# SHIELD-uSD-MIKROE-PMOD.net
KiCad netlist of a schematic drawn in Altium Designer
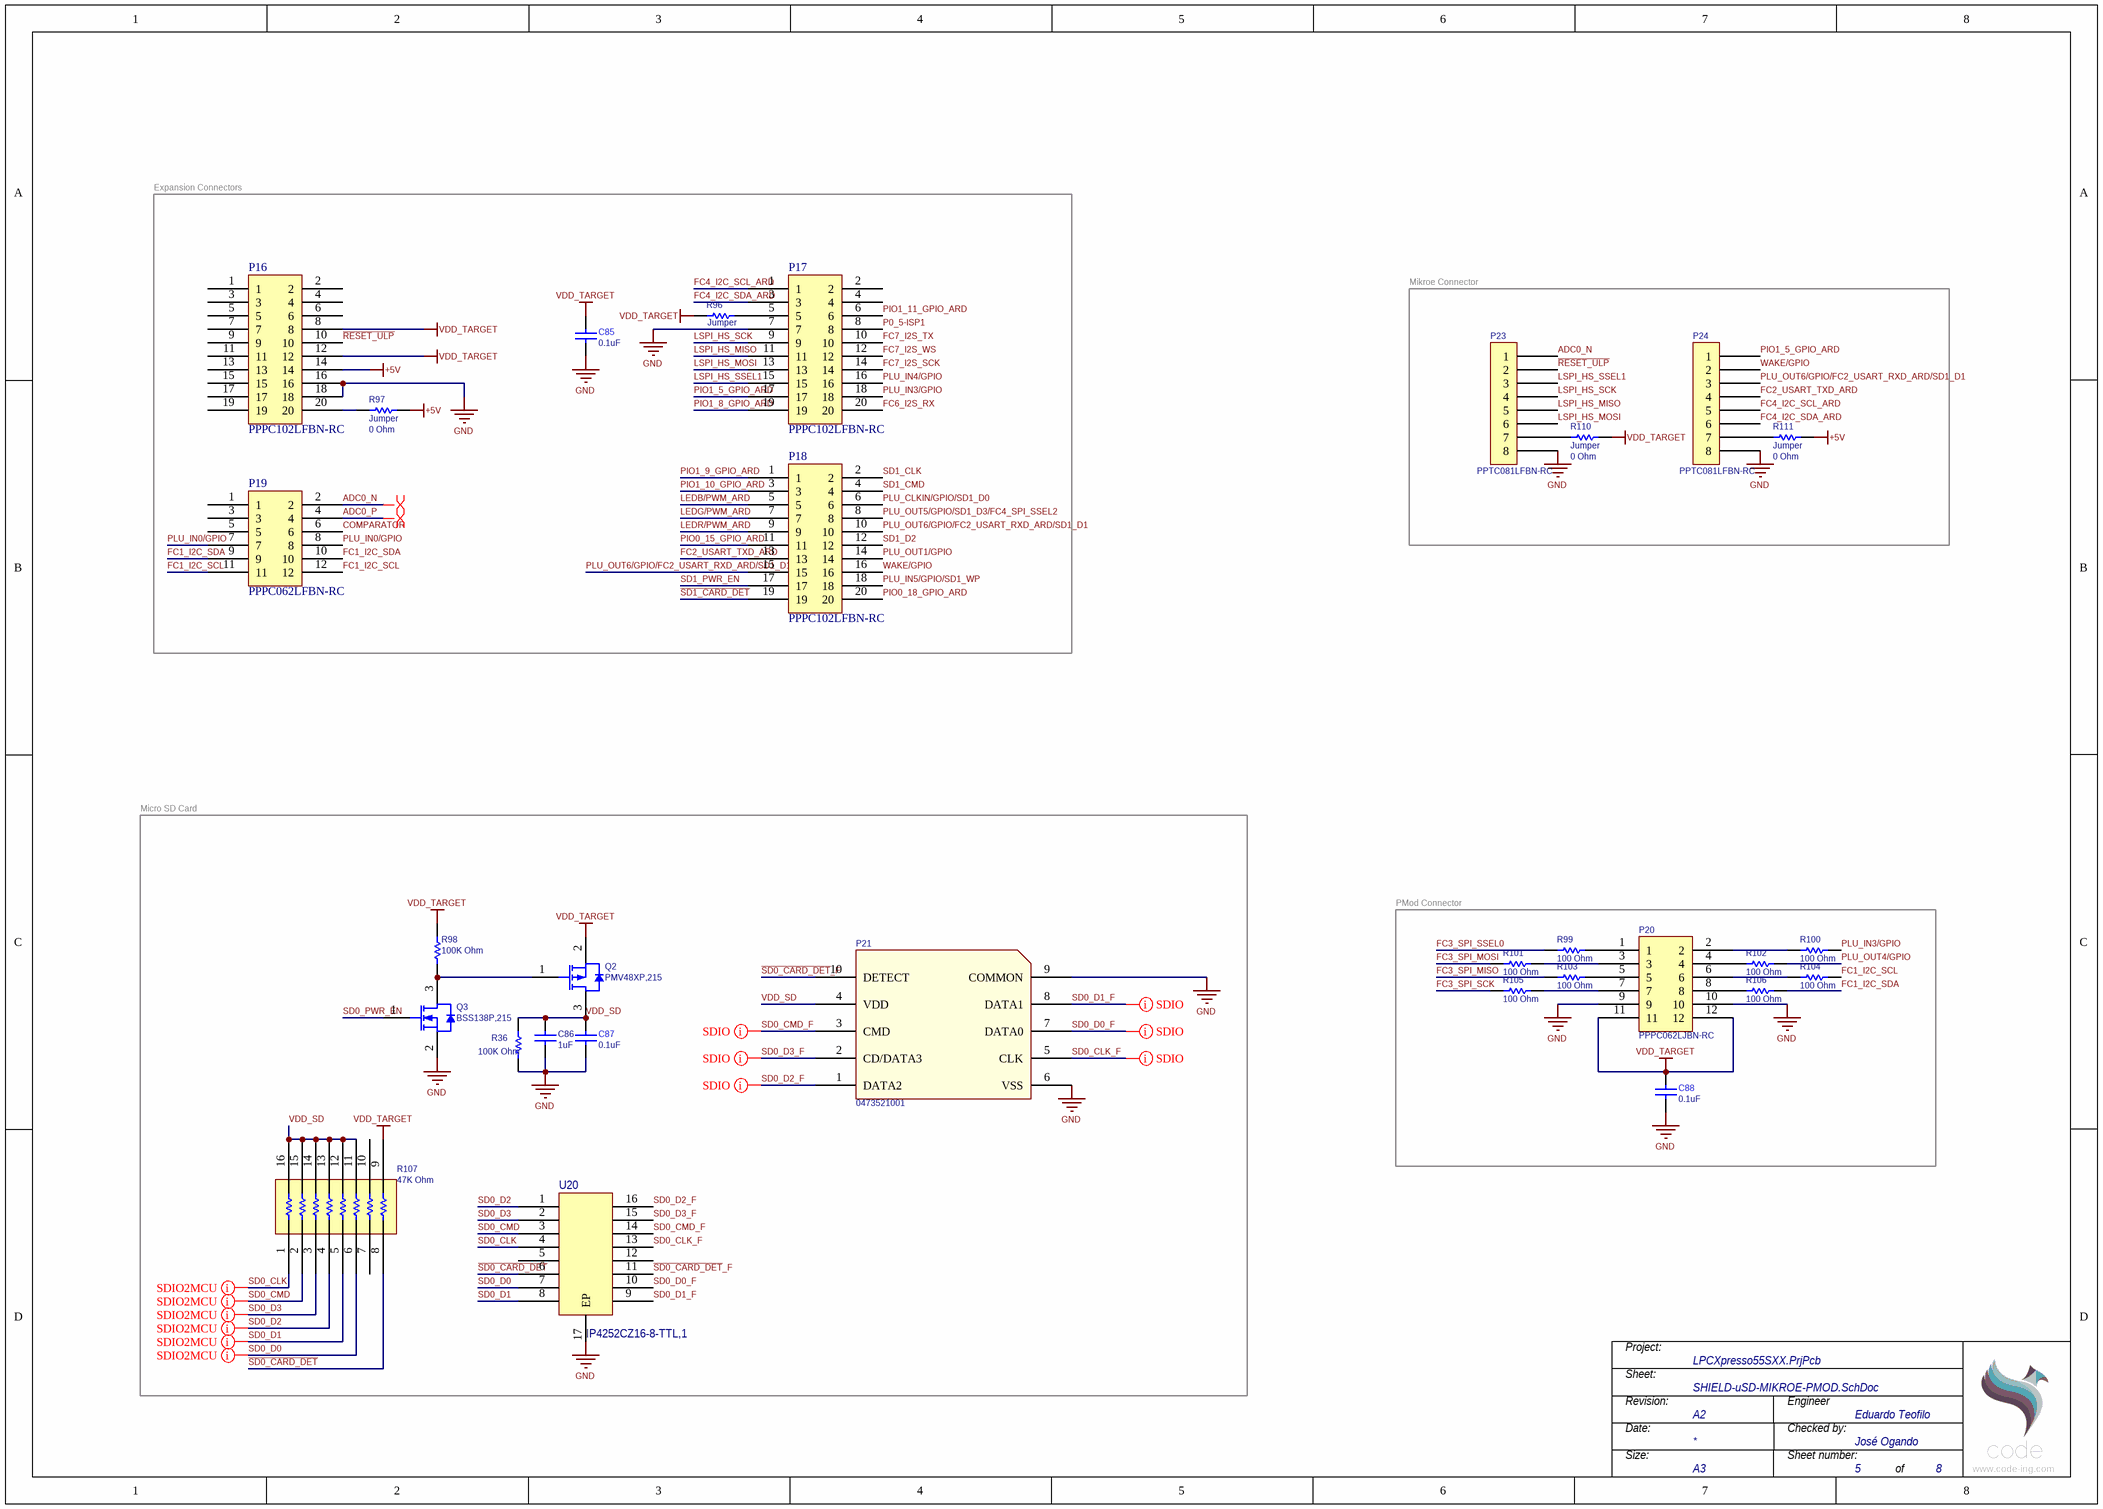
[diagram p0: SHIELD-uSD-MIKROE-PMOD.SchDoc]

(export (version "E")
  (design (tool "Eeschema 10.0.6"))
  (components
    (comp (ref "C85")
      (value "0.1uF")
      (footprint "CAPC1005")
      (description "Capacitor, Yageo, Ceramic, 0.1uF 10% 16V 0402 (1005) X7R")
      (fields
        (field (name "TOLERANCE") "10 %")
        (field (name "Comment") "CC0402KRX7R7BB104")
        (field (name "PUBLISHER") "Altium")
      )
      (libsource (lib "Altium Content Vault") (part "CMP-0001-00074-1"))
    )
    (comp (ref "C86")
      (value "1uF")
      (footprint "CAPC0402(1005)60_L")
      (description "CAP 1uF 10V -20% to +80% 0402 (1005 Metric) Thickness 0.6mm SMD")
      (fields (field (name "TOLERANCE") "-20% to +80%") (field (name "Comment") "CAP 1uF 10V 0402(1005)"))
      (libsource (lib "Altium Content Vault") (part "CMP-1034-02118-1"))
    )
    (comp (ref "C87")
      (value "0.1uF")
      (footprint "CAPC1005")
      (description "Capacitor, Yageo, Ceramic, 0.1uF 10% 16V 0402 (1005) X7R")
      (fields
        (field (name "TOLERANCE") "10 %")
        (field (name "Comment") "CC0402KRX7R7BB104")
        (field (name "PUBLISHER") "Altium")
      )
      (libsource (lib "Altium Content Vault") (part "CMP-0001-00074-1"))
    )
    (comp (ref "C88")
      (value "0.1uF")
      (footprint "CAPC1005")
      (description "Capacitor, Yageo, Ceramic, 0.1uF 10% 16V 0402 (1005) X7R")
      (fields
        (field (name "TOLERANCE") "10 %")
        (field (name "Comment") "CC0402KRX7R7BB104")
        (field (name "PUBLISHER") "Altium")
      )
      (libsource (lib "Altium Content Vault") (part "CMP-0001-00074-1"))
    )
    (comp (ref "P16")
      (value "PPPC102LFBN-RC")
      (footprint "PPPC102LFBN-RC")
      (description "CONN HEADER FMAL 20PS.1\" DL GOLD")
      (fields
        (field (name "MANUFACTURER") "Sullins Connector Solutions")
        (field (name "CREATED BY") "jvelasquez")
        (field (name "MODIFIED BY") "*")
      )
      (libsource (lib "Rectangular - Headers, Receptacles, Female Sockets") (part "PPPC102LFBN-RC"))
    )
    (comp (ref "P17")
      (value "PPPC102LFBN-RC")
      (footprint "PPPC102LFBN-RC")
      (description "CONN HEADER FMAL 20PS.1\" DL GOLD")
      (fields
        (field (name "MANUFACTURER") "Sullins Connector Solutions")
        (field (name "CREATED BY") "jvelasquez")
        (field (name "MODIFIED BY") "*")
      )
      (libsource (lib "Rectangular - Headers, Receptacles, Female Sockets") (part "PPPC102LFBN-RC"))
    )
    (comp (ref "P18")
      (value "PPPC102LFBN-RC")
      (footprint "PPPC102LFBN-RC")
      (description "CONN HEADER FMAL 20PS.1\" DL GOLD")
      (fields
        (field (name "MANUFACTURER") "Sullins Connector Solutions")
        (field (name "CREATED BY") "jvelasquez")
        (field (name "MODIFIED BY") "*")
      )
      (libsource (lib "Rectangular - Headers, Receptacles, Female Sockets") (part "PPPC102LFBN-RC"))
    )
    (comp (ref "P19")
      (value "PPPC062LFBN-RC")
      (footprint "PPPC062LFBN-RC")
      (description "CONN HEADER FMAL 12PS.1\" DL GOLD")
      (fields
        (field (name "MANUFACTURER") "Sullins Connector Solutions")
        (field (name "CREATED BY") "jvelasquez")
        (field (name "MODIFIED BY") "*")
      )
      (libsource (lib "Rectangular - Headers, Receptacles, Female Sockets") (part "PPPC062LFBN-RC"))
    )
    (comp (ref "P20")
      (value "PPPC062LJBN-RC")
      (footprint "PPPC062LJBN-RC")
      (description "CONN FEMALE 12POSDL .1\" R/A GOLD")
      (fields
        (field (name "MANUFACTURER") "Sullins Connector Solutions")
        (field (name "CREATED BY") "eteofilo")
        (field (name "MODIFIED BY") "*")
      )
      (libsource (lib "Rectangular - Headers, Receptacles, Female Sockets") (part "PPPC062LJBN-RC"))
    )
    (comp (ref "P21")
      (value "0473521001")
      (footprint "0473521001")
      (description "CONN MICRO SD CARD PUSH-PUSH R/A")
      (fields
        (field (name "MANUFACTURER") "Molex Inc")
        (field (name "CREATED BY") "eteofilo")
        (field (name "MODIFIED BY") "*")
      )
      (libsource (lib "Memory - PC Cards - Connectors") (part "0473521001"))
    )
    (comp (ref "P23")
      (value "PPTC081LFBN-RC")
      (footprint "Header 8x1")
      (description "CONN HEADER FEMALE 8POS .1\" TIN")
      (fields
        (field (name "MANUFACTURER") "Sullins Connector Solutions")
        (field (name "CREATED BY") "eteofilo")
        (field (name "MODIFIED BY") "*")
      )
      (libsource (lib "Rectangular - Headers, Receptacles, Female Sockets") (part "PPTC081LFBN-RC"))
    )
    (comp (ref "P24")
      (value "PPTC081LFBN-RC")
      (footprint "Header 8x1")
      (description "CONN HEADER FEMALE 8POS .1\" TIN")
      (fields
        (field (name "MANUFACTURER") "Sullins Connector Solutions")
        (field (name "CREATED BY") "eteofilo")
        (field (name "MODIFIED BY") "*")
      )
      (libsource (lib "Rectangular - Headers, Receptacles, Female Sockets") (part "PPTC081LFBN-RC"))
    )
    (comp (ref "Q2")
      (value "PMV48XP,215")
      (footprint "NXP-SOT23_M")
      (description "P-Channel Trench MOSFET, -20 V, -3.5 A, -55 to 150 degC, 3-Pin SOT23, Tape and Reel")
      (fields (field (name "MANUFACTURER") "NXP Semiconductors"))
      (libsource (lib "Altium Content Vault") (part "CMP-1258-00160-1"))
    )
    (comp (ref "Q3")
      (value "BSS138P,215")
      (footprint "NXP-SOT23_N")
      (description "N-Channel Trench MOSFET, 60 V, 0.36 A, -55 to 150 degC, 3-Pin SOT23, Tape and Reel")
      (fields (field (name "MANUFACTURER") "NXP Semiconductors"))
      (libsource (lib "Altium Content Vault") (part "NXP-NMOS-GSD-3_B"))
    )
    (comp (ref "R36")
      (value "100K Ohm")
      (footprint "RESC1005X40X25LL05T05")
      (description "Chip Resistor, 100 KOhm, +/- 1%, 100 mW, -55 to 155 degC, 0402 (1005 Metric), RoHS, Tape and Reel")
      (fields (field (name "TOLERANCE") "1%") (field (name "MANUFACTURER") "Basic Passives"))
      (libsource (lib "Altium Content Vault") (part "CMP-2002-00608-3"))
    )
    (comp (ref "R96")
      (value "Jumper")
      (footprint "RESC0402(1005)_L")
      (description "Jumper 0402 (1005 Metric)")
      (fields (field (name "TOLERANCE") "None"))
      (libsource (lib "Altium Content Vault") (part "CMP-1011-00001-1"))
    )
    (comp (ref "R97")
      (value "Jumper")
      (footprint "RESC0402(1005)_L")
      (description "Jumper 0402 (1005 Metric)")
      (fields (field (name "TOLERANCE") "None") (field (name "ALTIUM_VALUE") "0 Ohm"))
      (libsource (lib "Altium Content Vault") (part "CMP-1011-00001-1"))
    )
    (comp (ref "R98")
      (value "100K Ohm")
      (footprint "RESC1005X40X25LL05T05")
      (description "Chip Resistor, 100 KOhm, +/- 1%, 100 mW, -55 to 155 degC, 0402 (1005 Metric), RoHS, Tape and Reel")
      (fields (field (name "TOLERANCE") "1%") (field (name "MANUFACTURER") "Basic Passives"))
      (libsource (lib "Altium Content Vault") (part "CMP-2002-00608-3"))
    )
    (comp (ref "R99")
      (value "100 Ohm")
      (footprint "RESC0402(1005)_L")
      (description "100R 0.063W 5% 0402 (1005 Metric)  SMD")
      (fields (field (name "POWER") "0.063 W") (field (name "TOLERANCE") "5 %"))
      (libsource (lib "Altium Content Vault") (part "CMP-1011-00050-1"))
    )
    (comp (ref "R100")
      (value "100 Ohm")
      (footprint "RESC0402(1005)_L")
      (description "100R 0.063W 5% 0402 (1005 Metric)  SMD")
      (fields (field (name "POWER") "0.063 W") (field (name "TOLERANCE") "5 %"))
      (libsource (lib "Altium Content Vault") (part "CMP-1011-00050-1"))
    )
    (comp (ref "R101")
      (value "100 Ohm")
      (footprint "RESC0402(1005)_L")
      (description "100R 0.063W 5% 0402 (1005 Metric)  SMD")
      (fields (field (name "POWER") "0.063 W") (field (name "TOLERANCE") "5 %"))
      (libsource (lib "Altium Content Vault") (part "CMP-1011-00050-1"))
    )
    (comp (ref "R102")
      (value "100 Ohm")
      (footprint "RESC0402(1005)_L")
      (description "100R 0.063W 5% 0402 (1005 Metric)  SMD")
      (fields (field (name "POWER") "0.063 W") (field (name "TOLERANCE") "5 %"))
      (libsource (lib "Altium Content Vault") (part "CMP-1011-00050-1"))
    )
    (comp (ref "R103")
      (value "100 Ohm")
      (footprint "RESC0402(1005)_L")
      (description "100R 0.063W 5% 0402 (1005 Metric)  SMD")
      (fields (field (name "POWER") "0.063 W") (field (name "TOLERANCE") "5 %"))
      (libsource (lib "Altium Content Vault") (part "CMP-1011-00050-1"))
    )
    (comp (ref "R104")
      (value "100 Ohm")
      (footprint "RESC0402(1005)_L")
      (description "100R 0.063W 5% 0402 (1005 Metric)  SMD")
      (fields (field (name "POWER") "0.063 W") (field (name "TOLERANCE") "5 %"))
      (libsource (lib "Altium Content Vault") (part "CMP-1011-00050-1"))
    )
    (comp (ref "R105")
      (value "100 Ohm")
      (footprint "RESC0402(1005)_L")
      (description "100R 0.063W 5% 0402 (1005 Metric)  SMD")
      (fields (field (name "POWER") "0.063 W") (field (name "TOLERANCE") "5 %"))
      (libsource (lib "Altium Content Vault") (part "CMP-1011-00050-1"))
    )
    (comp (ref "R106")
      (value "100 Ohm")
      (footprint "RESC0402(1005)_L")
      (description "100R 0.063W 5% 0402 (1005 Metric)  SMD")
      (fields (field (name "POWER") "0.063 W") (field (name "TOLERANCE") "5 %"))
      (libsource (lib "Altium Content Vault") (part "CMP-1011-00050-1"))
    )
    (comp (ref "R107")
      (value "47K Ohm")
      (footprint "EXB-2HV473JV")
      (description "RES ARRAY 8 RES 47K OHM 1506")
      (fields
        (field (name "MANUFACTURER") "Panasonic Electronic Components")
        (field (name "MANUFACTURER PART #") "EXB-2HV473JV")
        (field (name "CREATED BY") "eteofilo")
        (field (name "MODIFIED BY") "*")
      )
      (libsource (lib "Resistor Networks, Arrays") (part "EXB-2HV473JV"))
    )
    (comp (ref "R110")
      (value "Jumper")
      (footprint "RESC0402(1005)_L")
      (description "Jumper 0402 (1005 Metric)")
      (fields (field (name "TOLERANCE") "None") (field (name "ALTIUM_VALUE") "0 Ohm"))
      (libsource (lib "Altium Content Vault") (part "CMP-1011-00001-1"))
    )
    (comp (ref "R111")
      (value "Jumper")
      (footprint "RESC0402(1005)_L")
      (description "Jumper 0402 (1005 Metric)")
      (fields (field (name "TOLERANCE") "None") (field (name "ALTIUM_VALUE") "0 Ohm"))
      (libsource (lib "Altium Content Vault") (part "CMP-1011-00001-1"))
    )
    (comp (ref "U20")
      (value "IP4252CZ16-8-TTL,1")
      (footprint "HUSON16")
      (fields
        (field (name "MANUFACTURER") "Nexperia USA Inc.")
        (field (name "CREATED BY") "eteofilo")
        (field (name "MODIFIED BY") "*")
      )
      (libsource (lib "EMI RFI Filters (LC, RC Networks)") (part "IP4252CZ16-8-TTL,1"))
    )
  )
  (nets
    (net (code "1") (name "+5V") (class "Default")
      (node (ref "P16") (pin "14") (pinfunction "14_14") (pintype "passive"))
      (node (ref "R111") (pin "1") (pinfunction "1_1") (pintype "passive"))
      (node (ref "R97") (pin "1") (pinfunction "1_1") (pintype "passive"))
    )
    (net (code "2") (name "/ADC0_N") (class "Default")
      (node (ref "P19") (pin "2") (pinfunction "2_2") (pintype "passive"))
      (node (ref "P23") (pin "1") (pinfunction "1_1") (pintype "passive"))
    )
    (net (code "3") (name "/ADC0_P") (class "Default")
      (node (ref "P19") (pin "4") (pinfunction "4_4") (pintype "passive"))
    )
    (net (code "4") (name "/COMPARATOR") (class "Default")
      (node (ref "P19") (pin "6") (pinfunction "6_6") (pintype "passive"))
    )
    (net (code "5") (name "/FC1_I2C_SCL") (class "Default")
      (node (ref "P19") (pin "11") (pinfunction "11_11") (pintype "passive"))
      (node (ref "P19") (pin "12") (pinfunction "12_12") (pintype "passive"))
      (node (ref "R104") (pin "2") (pinfunction "2_2") (pintype "passive"))
    )
    (net (code "6") (name "/FC1_I2C_SDA") (class "Default")
      (node (ref "P19") (pin "10") (pinfunction "10_10") (pintype "passive"))
      (node (ref "P19") (pin "9") (pinfunction "9_9") (pintype "passive"))
      (node (ref "R106") (pin "2") (pinfunction "2_2") (pintype "passive"))
    )
    (net (code "7") (name "/FC2_USART_TXD_ARD") (class "Default")
      (node (ref "P18") (pin "13") (pinfunction "13_13") (pintype "passive"))
      (node (ref "P24") (pin "4") (pinfunction "4_4") (pintype "passive"))
    )
    (net (code "8") (name "/FC3_SPI_MISO") (class "Default")
      (node (ref "R103") (pin "1") (pinfunction "1_1") (pintype "passive"))
    )
    (net (code "9") (name "/FC3_SPI_MOSI") (class "Default")
      (node (ref "R101") (pin "1") (pinfunction "1_1") (pintype "passive"))
    )
    (net (code "10") (name "/FC3_SPI_SCK") (class "Default")
      (node (ref "R105") (pin "1") (pinfunction "1_1") (pintype "passive"))
    )
    (net (code "11") (name "/FC3_SPI_SSEL0") (class "Default")
      (node (ref "R99") (pin "1") (pinfunction "1_1") (pintype "passive"))
    )
    (net (code "12") (name "/FC4_I2C_SCL_ARD") (class "Default")
      (node (ref "P17") (pin "1") (pinfunction "1_1") (pintype "passive"))
      (node (ref "P24") (pin "5") (pinfunction "5_5") (pintype "passive"))
    )
    (net (code "13") (name "/FC4_I2C_SDA_ARD") (class "Default")
      (node (ref "P17") (pin "3") (pinfunction "3_3") (pintype "passive"))
      (node (ref "P24") (pin "6") (pinfunction "6_6") (pintype "passive"))
    )
    (net (code "14") (name "/FC6_I2S_RX") (class "Default")
      (node (ref "P17") (pin "20") (pinfunction "20_20") (pintype "passive"))
    )
    (net (code "15") (name "/FC7_I2S_SCK") (class "Default")
      (node (ref "P17") (pin "14") (pinfunction "14_14") (pintype "passive"))
    )
    (net (code "16") (name "/FC7_I2S_TX") (class "Default")
      (node (ref "P17") (pin "10") (pinfunction "10_10") (pintype "passive"))
    )
    (net (code "17") (name "/FC7_I2S_WS") (class "Default")
      (node (ref "P17") (pin "12") (pinfunction "12_12") (pintype "passive"))
    )
    (net (code "18") (name "/LEDB{slash}PWM_ARD") (class "Default")
      (node (ref "P18") (pin "5") (pinfunction "5_5") (pintype "passive"))
    )
    (net (code "19") (name "/LEDG{slash}PWM_ARD") (class "Default")
      (node (ref "P18") (pin "7") (pinfunction "7_7") (pintype "passive"))
    )
    (net (code "20") (name "/LEDR{slash}PWM_ARD") (class "Default")
      (node (ref "P18") (pin "9") (pinfunction "9_9") (pintype "passive"))
    )
    (net (code "21") (name "/LSPI_HS_MISO") (class "Default")
      (node (ref "P17") (pin "11") (pinfunction "11_11") (pintype "passive"))
      (node (ref "P23") (pin "5") (pinfunction "5_5") (pintype "passive"))
    )
    (net (code "22") (name "/LSPI_HS_MOSI") (class "Default")
      (node (ref "P17") (pin "13") (pinfunction "13_13") (pintype "passive"))
      (node (ref "P23") (pin "6") (pinfunction "6_6") (pintype "passive"))
    )
    (net (code "23") (name "/LSPI_HS_SCK") (class "Default")
      (node (ref "P17") (pin "9") (pinfunction "9_9") (pintype "passive"))
      (node (ref "P23") (pin "4") (pinfunction "4_4") (pintype "passive"))
    )
    (net (code "24") (name "/LSPI_HS_SSEL1") (class "Default")
      (node (ref "P17") (pin "15") (pinfunction "15_15") (pintype "passive"))
      (node (ref "P23") (pin "3") (pinfunction "3_3") (pintype "passive"))
    )
    (net (code "25") (name "/P0_5-ISP1") (class "Default")
      (node (ref "P17") (pin "8") (pinfunction "8_8") (pintype "passive"))
    )
    (net (code "26") (name "/PIO0_15_GPIO_ARD") (class "Default")
      (node (ref "P18") (pin "11") (pinfunction "11_11") (pintype "passive"))
    )
    (net (code "27") (name "/PIO0_18_GPIO_ARD") (class "Default")
      (node (ref "P18") (pin "20") (pinfunction "20_20") (pintype "passive"))
    )
    (net (code "28") (name "/PIO1_5_GPIO_ARD") (class "Default")
      (node (ref "P17") (pin "17") (pinfunction "17_17") (pintype "passive"))
      (node (ref "P24") (pin "1") (pinfunction "1_1") (pintype "passive"))
    )
    (net (code "29") (name "/PIO1_8_GPIO_ARD") (class "Default")
      (node (ref "P17") (pin "19") (pinfunction "19_19") (pintype "passive"))
    )
    (net (code "30") (name "/PIO1_9_GPIO_ARD") (class "Default")
      (node (ref "P18") (pin "1") (pinfunction "1_1") (pintype "passive"))
    )
    (net (code "31") (name "/PIO1_10_GPIO_ARD") (class "Default")
      (node (ref "P18") (pin "3") (pinfunction "3_3") (pintype "passive"))
    )
    (net (code "32") (name "/PIO1_11_GPIO_ARD") (class "Default")
      (node (ref "P17") (pin "6") (pinfunction "6_6") (pintype "passive"))
    )
    (net (code "33") (name "/PLU_CLKIN{slash}GPIO{slash}SD1_D0") (class "Default")
      (node (ref "P18") (pin "6") (pinfunction "6_6") (pintype "passive"))
    )
    (net (code "34") (name "/PLU_IN0{slash}GPIO") (class "Default")
      (node (ref "P19") (pin "7") (pinfunction "7_7") (pintype "passive"))
      (node (ref "P19") (pin "8") (pinfunction "8_8") (pintype "passive"))
    )
    (net (code "35") (name "/PLU_IN3{slash}GPIO") (class "Default")
      (node (ref "P17") (pin "18") (pinfunction "18_18") (pintype "passive"))
      (node (ref "R100") (pin "2") (pinfunction "2_2") (pintype "passive"))
    )
    (net (code "36") (name "/PLU_IN4{slash}GPIO") (class "Default")
      (node (ref "P17") (pin "16") (pinfunction "16_16") (pintype "passive"))
    )
    (net (code "37") (name "/PLU_IN5{slash}GPIO{slash}SD1_WP") (class "Default")
      (node (ref "P18") (pin "18") (pinfunction "18_18") (pintype "passive"))
    )
    (net (code "38") (name "/PLU_OUT1{slash}GPIO") (class "Default")
      (node (ref "P18") (pin "14") (pinfunction "14_14") (pintype "passive"))
    )
    (net (code "39") (name "/PLU_OUT4{slash}GPIO") (class "Default")
      (node (ref "R102") (pin "2") (pinfunction "2_2") (pintype "passive"))
    )
    (net (code "40") (name "/PLU_OUT5{slash}GPIO{slash}SD1_D3{slash}FC4_SPI_SSEL2") (class "Default")
      (node (ref "P18") (pin "8") (pinfunction "8_8") (pintype "passive"))
    )
    (net (code "41") (name "/PLU_OUT6{slash}GPIO{slash}FC2_USART_RXD_ARD{slash}SD1_D1") (class "Default")
      (node (ref "P18") (pin "10") (pinfunction "10_10") (pintype "passive"))
      (node (ref "P18") (pin "15") (pinfunction "15_15") (pintype "passive"))
      (node (ref "P24") (pin "3") (pinfunction "3_3") (pintype "passive"))
    )
    (net (code "42") (name "/SD0_CLK") (class "Default")
      (node (ref "R107") (pin "1") (pinfunction "1_1") (pintype "passive"))
      (node (ref "U20") (pin "4") (pintype "passive"))
    )
    (net (code "43") (name "/SD0_CLK_F") (class "Default")
      (node (ref "P21") (pin "5") (pinfunction "CLK_5") (pintype "passive"))
      (node (ref "U20") (pin "13") (pintype "passive"))
    )
    (net (code "44") (name "/SD0_CMD") (class "Default")
      (node (ref "R107") (pin "2") (pinfunction "2_2") (pintype "passive"))
      (node (ref "U20") (pin "3") (pintype "passive"))
    )
    (net (code "45") (name "/SD0_CMD_F") (class "Default")
      (node (ref "P21") (pin "3") (pinfunction "CMD_3") (pintype "passive"))
      (node (ref "U20") (pin "14") (pintype "passive"))
    )
    (net (code "46") (name "/SD0_D0") (class "Default")
      (node (ref "R107") (pin "6") (pinfunction "6_6") (pintype "passive"))
      (node (ref "U20") (pin "7") (pintype "passive"))
    )
    (net (code "47") (name "/SD0_D0_F") (class "Default")
      (node (ref "P21") (pin "7") (pinfunction "DATA0_7") (pintype "passive"))
      (node (ref "U20") (pin "10") (pintype "passive"))
    )
    (net (code "48") (name "/SD0_D1") (class "Default")
      (node (ref "R107") (pin "5") (pinfunction "5_5") (pintype "passive"))
      (node (ref "U20") (pin "8") (pintype "passive"))
    )
    (net (code "49") (name "/SD0_D1_F") (class "Default")
      (node (ref "P21") (pin "8") (pinfunction "DATA1_8") (pintype "passive"))
      (node (ref "U20") (pin "9") (pintype "passive"))
    )
    (net (code "50") (name "/SD0_D2") (class "Default")
      (node (ref "R107") (pin "4") (pinfunction "4_4") (pintype "passive"))
      (node (ref "U20") (pin "1") (pintype "passive"))
    )
    (net (code "51") (name "/SD0_D2_F") (class "Default")
      (node (ref "P21") (pin "1") (pinfunction "DATA2_1") (pintype "passive"))
      (node (ref "U20") (pin "16") (pintype "passive"))
    )
    (net (code "52") (name "/SD0_D3") (class "Default")
      (node (ref "R107") (pin "3") (pinfunction "3_3") (pintype "passive"))
      (node (ref "U20") (pin "2") (pintype "passive"))
    )
    (net (code "53") (name "/SD0_D3_F") (class "Default")
      (node (ref "P21") (pin "2") (pinfunction "CD/DATA3_2") (pintype "passive"))
      (node (ref "U20") (pin "15") (pintype "passive"))
    )
    (net (code "54") (name "/SD0_PWR_EN") (class "Default")
      (node (ref "Q3") (pin "1") (pinfunction "G_1") (pintype "passive"))
    )
    (net (code "55") (name "/SD1_CLK") (class "Default")
      (node (ref "P18") (pin "2") (pinfunction "2_2") (pintype "passive"))
    )
    (net (code "56") (name "/SD1_CMD") (class "Default")
      (node (ref "P18") (pin "4") (pinfunction "4_4") (pintype "passive"))
    )
    (net (code "57") (name "/SD1_D2") (class "Default")
      (node (ref "P18") (pin "12") (pinfunction "12_12") (pintype "passive"))
    )
    (net (code "58") (name "/SD1_PWR_EN") (class "Default")
      (node (ref "P18") (pin "17") (pinfunction "17_17") (pintype "passive"))
    )
    (net (code "59") (name "/VDD_SD") (class "Default")
      (node (ref "C86") (pin "2") (pinfunction "2_2") (pintype "passive"))
      (node (ref "C87") (pin "1") (pinfunction "1_1") (pintype "passive"))
      (node (ref "P21") (pin "4") (pinfunction "VDD_4") (pintype "passive"))
      (node (ref "Q2") (pin "3") (pinfunction "D_3") (pintype "passive"))
      (node (ref "R107") (pin "11") (pinfunction "11_11") (pintype "passive"))
      (node (ref "R107") (pin "12") (pinfunction "12_12") (pintype "passive"))
      (node (ref "R107") (pin "13") (pinfunction "13_13") (pintype "passive"))
      (node (ref "R107") (pin "14") (pinfunction "14_14") (pintype "passive"))
      (node (ref "R107") (pin "15") (pinfunction "15_15") (pintype "passive"))
      (node (ref "R107") (pin "16") (pinfunction "16_16") (pintype "passive"))
      (node (ref "R36") (pin "2") (pinfunction "2_2") (pintype "passive"))
    )
    (net (code "60") (name "/WAKE{slash}GPIO") (class "Default")
      (node (ref "P18") (pin "16") (pinfunction "16_16") (pintype "passive"))
      (node (ref "P24") (pin "2") (pinfunction "2_2") (pintype "passive"))
    )
    (net (code "61") (name "/~{RESET_ULP}") (class "Default")
      (node (ref "P16") (pin "10") (pinfunction "10_10") (pintype "passive"))
      (node (ref "P23") (pin "2") (pinfunction "2_2") (pintype "passive"))
    )
    (net (code "62") (name "/~{SD0_CARD_DET}") (class "Default")
      (node (ref "R107") (pin "8") (pinfunction "8_8") (pintype "passive"))
      (node (ref "U20") (pin "6") (pintype "passive"))
    )
    (net (code "63") (name "/~{SD0_CARD_DET}_F") (class "Default")
      (node (ref "P21") (pin "10") (pinfunction "DETECT_10") (pintype "passive"))
      (node (ref "U20") (pin "11") (pintype "passive"))
    )
    (net (code "64") (name "/~{SD1_CARD_DET}") (class "Default")
      (node (ref "P18") (pin "19") (pinfunction "19_19") (pintype "passive"))
    )
    (net (code "65") (name "GND") (class "Default")
      (node (ref "C85") (pin "2") (pinfunction "2_2") (pintype "passive"))
      (node (ref "C86") (pin "1") (pinfunction "1_1") (pintype "passive"))
      (node (ref "C87") (pin "2") (pinfunction "2_2") (pintype "passive"))
      (node (ref "C88") (pin "2") (pinfunction "2_2") (pintype "passive"))
      (node (ref "P16") (pin "16") (pinfunction "16_16") (pintype "passive"))
      (node (ref "P16") (pin "18") (pinfunction "18_18") (pintype "passive"))
      (node (ref "P17") (pin "7") (pinfunction "7_7") (pintype "passive"))
      (node (ref "P20") (pin "10") (pinfunction "10_10") (pintype "passive"))
      (node (ref "P20") (pin "9") (pinfunction "9_9") (pintype "passive"))
      (node (ref "P21") (pin "6") (pinfunction "VSS_6") (pintype "passive"))
      (node (ref "P21") (pin "9") (pinfunction "COMMON_9") (pintype "passive"))
      (node (ref "P23") (pin "8") (pinfunction "8_8") (pintype "passive"))
      (node (ref "P24") (pin "8") (pinfunction "8_8") (pintype "passive"))
      (node (ref "Q3") (pin "2") (pinfunction "S_2") (pintype "passive"))
      (node (ref "R36") (pin "1") (pinfunction "1_1") (pintype "passive"))
      (node (ref "U20") (pin "17") (pinfunction "EP_17") (pintype "passive"))
    )
    (net (code "66") (name "Net-(P16-Pad20)") (class "Default")
      (node (ref "P16") (pin "20") (pinfunction "20_20") (pintype "passive"))
      (node (ref "R97") (pin "2") (pinfunction "2_2") (pintype "passive"))
    )
    (net (code "67") (name "Net-(P17-Pad5)") (class "Default")
      (node (ref "P17") (pin "5") (pinfunction "5_5") (pintype "passive"))
      (node (ref "R96") (pin "1") (pinfunction "1_1") (pintype "passive"))
    )
    (net (code "68") (name "Net-(P20-Pad1)") (class "Default")
      (node (ref "P20") (pin "1") (pinfunction "1_1") (pintype "passive"))
      (node (ref "R99") (pin "2") (pinfunction "2_2") (pintype "passive"))
    )
    (net (code "69") (name "Net-(P20-Pad2)") (class "Default")
      (node (ref "P20") (pin "2") (pinfunction "2_2") (pintype "passive"))
      (node (ref "R100") (pin "1") (pinfunction "1_1") (pintype "passive"))
    )
    (net (code "70") (name "Net-(P20-Pad3)") (class "Default")
      (node (ref "P20") (pin "3") (pinfunction "3_3") (pintype "passive"))
      (node (ref "R101") (pin "2") (pinfunction "2_2") (pintype "passive"))
    )
    (net (code "71") (name "Net-(P20-Pad4)") (class "Default")
      (node (ref "P20") (pin "4") (pinfunction "4_4") (pintype "passive"))
      (node (ref "R102") (pin "1") (pinfunction "1_1") (pintype "passive"))
    )
    (net (code "72") (name "Net-(P20-Pad5)") (class "Default")
      (node (ref "P20") (pin "5") (pinfunction "5_5") (pintype "passive"))
      (node (ref "R103") (pin "2") (pinfunction "2_2") (pintype "passive"))
    )
    (net (code "73") (name "Net-(P20-Pad6)") (class "Default")
      (node (ref "P20") (pin "6") (pinfunction "6_6") (pintype "passive"))
      (node (ref "R104") (pin "1") (pinfunction "1_1") (pintype "passive"))
    )
    (net (code "74") (name "Net-(P20-Pad7)") (class "Default")
      (node (ref "P20") (pin "7") (pinfunction "7_7") (pintype "passive"))
      (node (ref "R105") (pin "2") (pinfunction "2_2") (pintype "passive"))
    )
    (net (code "75") (name "Net-(P20-Pad8)") (class "Default")
      (node (ref "P20") (pin "8") (pinfunction "8_8") (pintype "passive"))
      (node (ref "R106") (pin "1") (pinfunction "1_1") (pintype "passive"))
    )
    (net (code "76") (name "Net-(P23-Pad7)") (class "Default")
      (node (ref "P23") (pin "7") (pinfunction "7_7") (pintype "passive"))
      (node (ref "R110") (pin "2") (pinfunction "2_2") (pintype "passive"))
    )
    (net (code "77") (name "Net-(P24-Pad7)") (class "Default")
      (node (ref "P24") (pin "7") (pinfunction "7_7") (pintype "passive"))
      (node (ref "R111") (pin "2") (pinfunction "2_2") (pintype "passive"))
    )
    (net (code "78") (name "Net-(Q2-G)") (class "Default")
      (node (ref "Q2") (pin "1") (pinfunction "G_1") (pintype "passive"))
      (node (ref "Q3") (pin "3") (pinfunction "D_3") (pintype "passive"))
      (node (ref "R98") (pin "1") (pinfunction "1_1") (pintype "passive"))
    )
    (net (code "79") (name "VDD_TARGET") (class "Default")
      (node (ref "C85") (pin "1") (pinfunction "1_1") (pintype "passive"))
      (node (ref "C88") (pin "1") (pinfunction "1_1") (pintype "passive"))
      (node (ref "P16") (pin "12") (pinfunction "12_12") (pintype "passive"))
      (node (ref "P16") (pin "8") (pinfunction "8_8") (pintype "passive"))
      (node (ref "P20") (pin "11") (pinfunction "11_11") (pintype "passive"))
      (node (ref "P20") (pin "12") (pinfunction "12_12") (pintype "passive"))
      (node (ref "Q2") (pin "2") (pinfunction "S_2") (pintype "passive"))
      (node (ref "R107") (pin "9") (pinfunction "9_9") (pintype "passive"))
      (node (ref "R110") (pin "1") (pinfunction "1_1") (pintype "passive"))
      (node (ref "R96") (pin "2") (pinfunction "2_2") (pintype "passive"))
      (node (ref "R98") (pin "2") (pinfunction "2_2") (pintype "passive"))
    )
    (net (code "80") (name "unconnected-(P16-Pad1)") (class "Default")
      (node (ref "P16") (pin "1") (pinfunction "1_1") (pintype "passive"))
    )
    (net (code "81") (name "unconnected-(P16-Pad2)") (class "Default")
      (node (ref "P16") (pin "2") (pinfunction "2_2") (pintype "passive"))
    )
    (net (code "82") (name "unconnected-(P16-Pad3)") (class "Default")
      (node (ref "P16") (pin "3") (pinfunction "3_3") (pintype "passive"))
    )
    (net (code "83") (name "unconnected-(P16-Pad4)") (class "Default")
      (node (ref "P16") (pin "4") (pinfunction "4_4") (pintype "passive"))
    )
    (net (code "84") (name "unconnected-(P16-Pad5)") (class "Default")
      (node (ref "P16") (pin "5") (pinfunction "5_5") (pintype "passive"))
    )
    (net (code "85") (name "unconnected-(P16-Pad6)") (class "Default")
      (node (ref "P16") (pin "6") (pinfunction "6_6") (pintype "passive"))
    )
    (net (code "86") (name "unconnected-(P16-Pad7)") (class "Default")
      (node (ref "P16") (pin "7") (pinfunction "7_7") (pintype "passive"))
    )
    (net (code "87") (name "unconnected-(P16-Pad9)") (class "Default")
      (node (ref "P16") (pin "9") (pinfunction "9_9") (pintype "passive"))
    )
    (net (code "88") (name "unconnected-(P16-Pad11)") (class "Default")
      (node (ref "P16") (pin "11") (pinfunction "11_11") (pintype "passive"))
    )
    (net (code "89") (name "unconnected-(P16-Pad13)") (class "Default")
      (node (ref "P16") (pin "13") (pinfunction "13_13") (pintype "passive"))
    )
    (net (code "90") (name "unconnected-(P16-Pad15)") (class "Default")
      (node (ref "P16") (pin "15") (pinfunction "15_15") (pintype "passive"))
    )
    (net (code "91") (name "unconnected-(P16-Pad17)") (class "Default")
      (node (ref "P16") (pin "17") (pinfunction "17_17") (pintype "passive"))
    )
    (net (code "92") (name "unconnected-(P16-Pad19)") (class "Default")
      (node (ref "P16") (pin "19") (pinfunction "19_19") (pintype "passive"))
    )
    (net (code "93") (name "unconnected-(P17-Pad2)") (class "Default")
      (node (ref "P17") (pin "2") (pinfunction "2_2") (pintype "passive"))
    )
    (net (code "94") (name "unconnected-(P17-Pad4)") (class "Default")
      (node (ref "P17") (pin "4") (pinfunction "4_4") (pintype "passive"))
    )
    (net (code "95") (name "unconnected-(P19-Pad1)") (class "Default")
      (node (ref "P19") (pin "1") (pinfunction "1_1") (pintype "passive"))
    )
    (net (code "96") (name "unconnected-(P19-Pad3)") (class "Default")
      (node (ref "P19") (pin "3") (pinfunction "3_3") (pintype "passive"))
    )
    (net (code "97") (name "unconnected-(P19-Pad5)") (class "Default")
      (node (ref "P19") (pin "5") (pinfunction "5_5") (pintype "passive"))
    )
    (net (code "98") (name "unconnected-(R107-Pad7)") (class "Default")
      (node (ref "R107") (pin "7") (pinfunction "7_7") (pintype "passive"))
    )
    (net (code "99") (name "unconnected-(R107-Pad10)") (class "Default")
      (node (ref "R107") (pin "10") (pinfunction "10_10") (pintype "passive"))
    )
    (net (code "100") (name "unconnected-(U20-Pad5)") (class "Default")
      (node (ref "U20") (pin "5") (pintype "passive"))
    )
    (net (code "101") (name "unconnected-(U20-Pad12)") (class "Default")
      (node (ref "U20") (pin "12") (pintype "passive"))
    )
  )
)
